# DTB217-AW1.net
KiCad netlist of a schematic drawn in Altium Designer
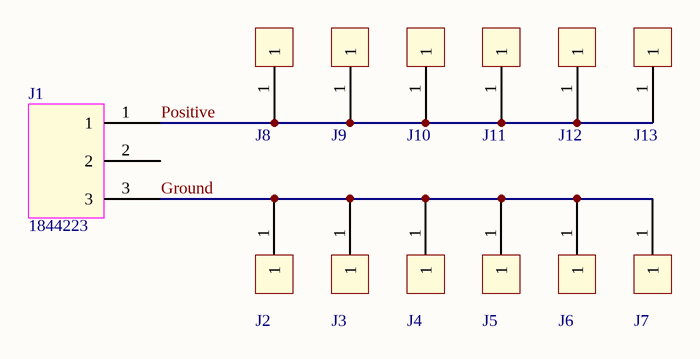
[diagram p0: DTB217-AW1.SchDoc]

(export (version "E")
  (design (tool "Eeschema 10.0.6"))
  (components
    (comp (ref "J1")
      (value "1844223")
      (footprint "1844223")
      (fields (field (name "MANUFACTURER") "Phoenix Contact"))
      (libsource (lib "Allen_Integrated_Library") (part "1844223"))
    )
    (comp (ref "J2")
      (value "CONN HEADER VERT 1POS")
      (footprint "TSW-101-17-G-S")
      (description "Connector Header Through Hole 1 position")
      (fields (field (name "MANUFACTURER") "Samtec Inc"))
      (libsource (lib "andre-altium-lib") (part "TSW-101-17-G-S"))
    )
    (comp (ref "J3")
      (value "CONN HEADER VERT 1POS")
      (footprint "TSW-101-17-G-S")
      (description "Connector Header Through Hole 1 position")
      (fields (field (name "MANUFACTURER") "Samtec Inc"))
      (libsource (lib "andre-altium-lib") (part "TSW-101-17-G-S"))
    )
    (comp (ref "J4")
      (value "CONN HEADER VERT 1POS")
      (footprint "TSW-101-17-G-S")
      (description "Connector Header Through Hole 1 position")
      (fields (field (name "MANUFACTURER") "Samtec Inc"))
      (libsource (lib "andre-altium-lib") (part "TSW-101-17-G-S"))
    )
    (comp (ref "J5")
      (value "CONN HEADER VERT 1POS")
      (footprint "TSW-101-17-G-S")
      (description "Connector Header Through Hole 1 position")
      (fields (field (name "MANUFACTURER") "Samtec Inc"))
      (libsource (lib "andre-altium-lib") (part "TSW-101-17-G-S"))
    )
    (comp (ref "J6")
      (value "CONN HEADER VERT 1POS")
      (footprint "TSW-101-17-G-S")
      (description "Connector Header Through Hole 1 position")
      (fields (field (name "MANUFACTURER") "Samtec Inc"))
      (libsource (lib "andre-altium-lib") (part "TSW-101-17-G-S"))
    )
    (comp (ref "J7")
      (value "CONN HEADER VERT 1POS")
      (footprint "TSW-101-17-G-S")
      (description "Connector Header Through Hole 1 position")
      (fields (field (name "MANUFACTURER") "Samtec Inc"))
      (libsource (lib "andre-altium-lib") (part "TSW-101-17-G-S"))
    )
    (comp (ref "J8")
      (value "CONN HEADER VERT 1POS")
      (footprint "TSW-101-17-G-S")
      (description "Connector Header Through Hole 1 position")
      (fields (field (name "MANUFACTURER") "Samtec Inc"))
      (libsource (lib "") (part "TSW-101-17-G-S_1"))
    )
    (comp (ref "J9")
      (value "CONN HEADER VERT 1POS")
      (footprint "TSW-101-17-G-S")
      (description "Connector Header Through Hole 1 position")
      (fields (field (name "MANUFACTURER") "Samtec Inc"))
      (libsource (lib "") (part "TSW-101-17-G-S_1"))
    )
    (comp (ref "J10")
      (value "CONN HEADER VERT 1POS")
      (footprint "TSW-101-17-G-S")
      (description "Connector Header Through Hole 1 position")
      (fields (field (name "MANUFACTURER") "Samtec Inc"))
      (libsource (lib "") (part "TSW-101-17-G-S_1"))
    )
    (comp (ref "J11")
      (value "CONN HEADER VERT 1POS")
      (footprint "TSW-101-17-G-S")
      (description "Connector Header Through Hole 1 position")
      (fields (field (name "MANUFACTURER") "Samtec Inc"))
      (libsource (lib "") (part "TSW-101-17-G-S_1"))
    )
    (comp (ref "J12")
      (value "CONN HEADER VERT 1POS")
      (footprint "TSW-101-17-G-S")
      (description "Connector Header Through Hole 1 position")
      (fields (field (name "MANUFACTURER") "Samtec Inc"))
      (libsource (lib "") (part "TSW-101-17-G-S_1"))
    )
    (comp (ref "J13")
      (value "CONN HEADER VERT 1POS")
      (footprint "TSW-101-17-G-S")
      (description "Connector Header Through Hole 1 position")
      (fields (field (name "MANUFACTURER") "Samtec Inc"))
      (libsource (lib "") (part "TSW-101-17-G-S_1"))
    )
  )
  (nets
    (net (code "1") (name "/Ground") (class "Default")
      (node (ref "J1") (pin "3") (pinfunction "3_3") (pintype "passive"))
      (node (ref "J2") (pin "1") (pinfunction "1_1") (pintype "passive"))
      (node (ref "J3") (pin "1") (pinfunction "1_1") (pintype "passive"))
      (node (ref "J4") (pin "1") (pinfunction "1_1") (pintype "passive"))
      (node (ref "J5") (pin "1") (pinfunction "1_1") (pintype "passive"))
      (node (ref "J6") (pin "1") (pinfunction "1_1") (pintype "passive"))
      (node (ref "J7") (pin "1") (pinfunction "1_1") (pintype "passive"))
    )
    (net (code "2") (name "/Positive") (class "Default")
      (node (ref "J1") (pin "1") (pinfunction "1_1") (pintype "passive"))
      (node (ref "J10") (pin "1") (pinfunction "1_1") (pintype "passive"))
      (node (ref "J11") (pin "1") (pinfunction "1_1") (pintype "passive"))
      (node (ref "J12") (pin "1") (pinfunction "1_1") (pintype "passive"))
      (node (ref "J13") (pin "1") (pinfunction "1_1") (pintype "passive"))
      (node (ref "J8") (pin "1") (pinfunction "1_1") (pintype "passive"))
      (node (ref "J9") (pin "1") (pinfunction "1_1") (pintype "passive"))
    )
    (net (code "3") (name "unconnected-(J1-Pad2)") (class "Default")
      (node (ref "J1") (pin "2") (pinfunction "2_2") (pintype "passive"))
    )
  )
)
